# main_board.net
KiCad netlist of a schematic drawn in EAGLE
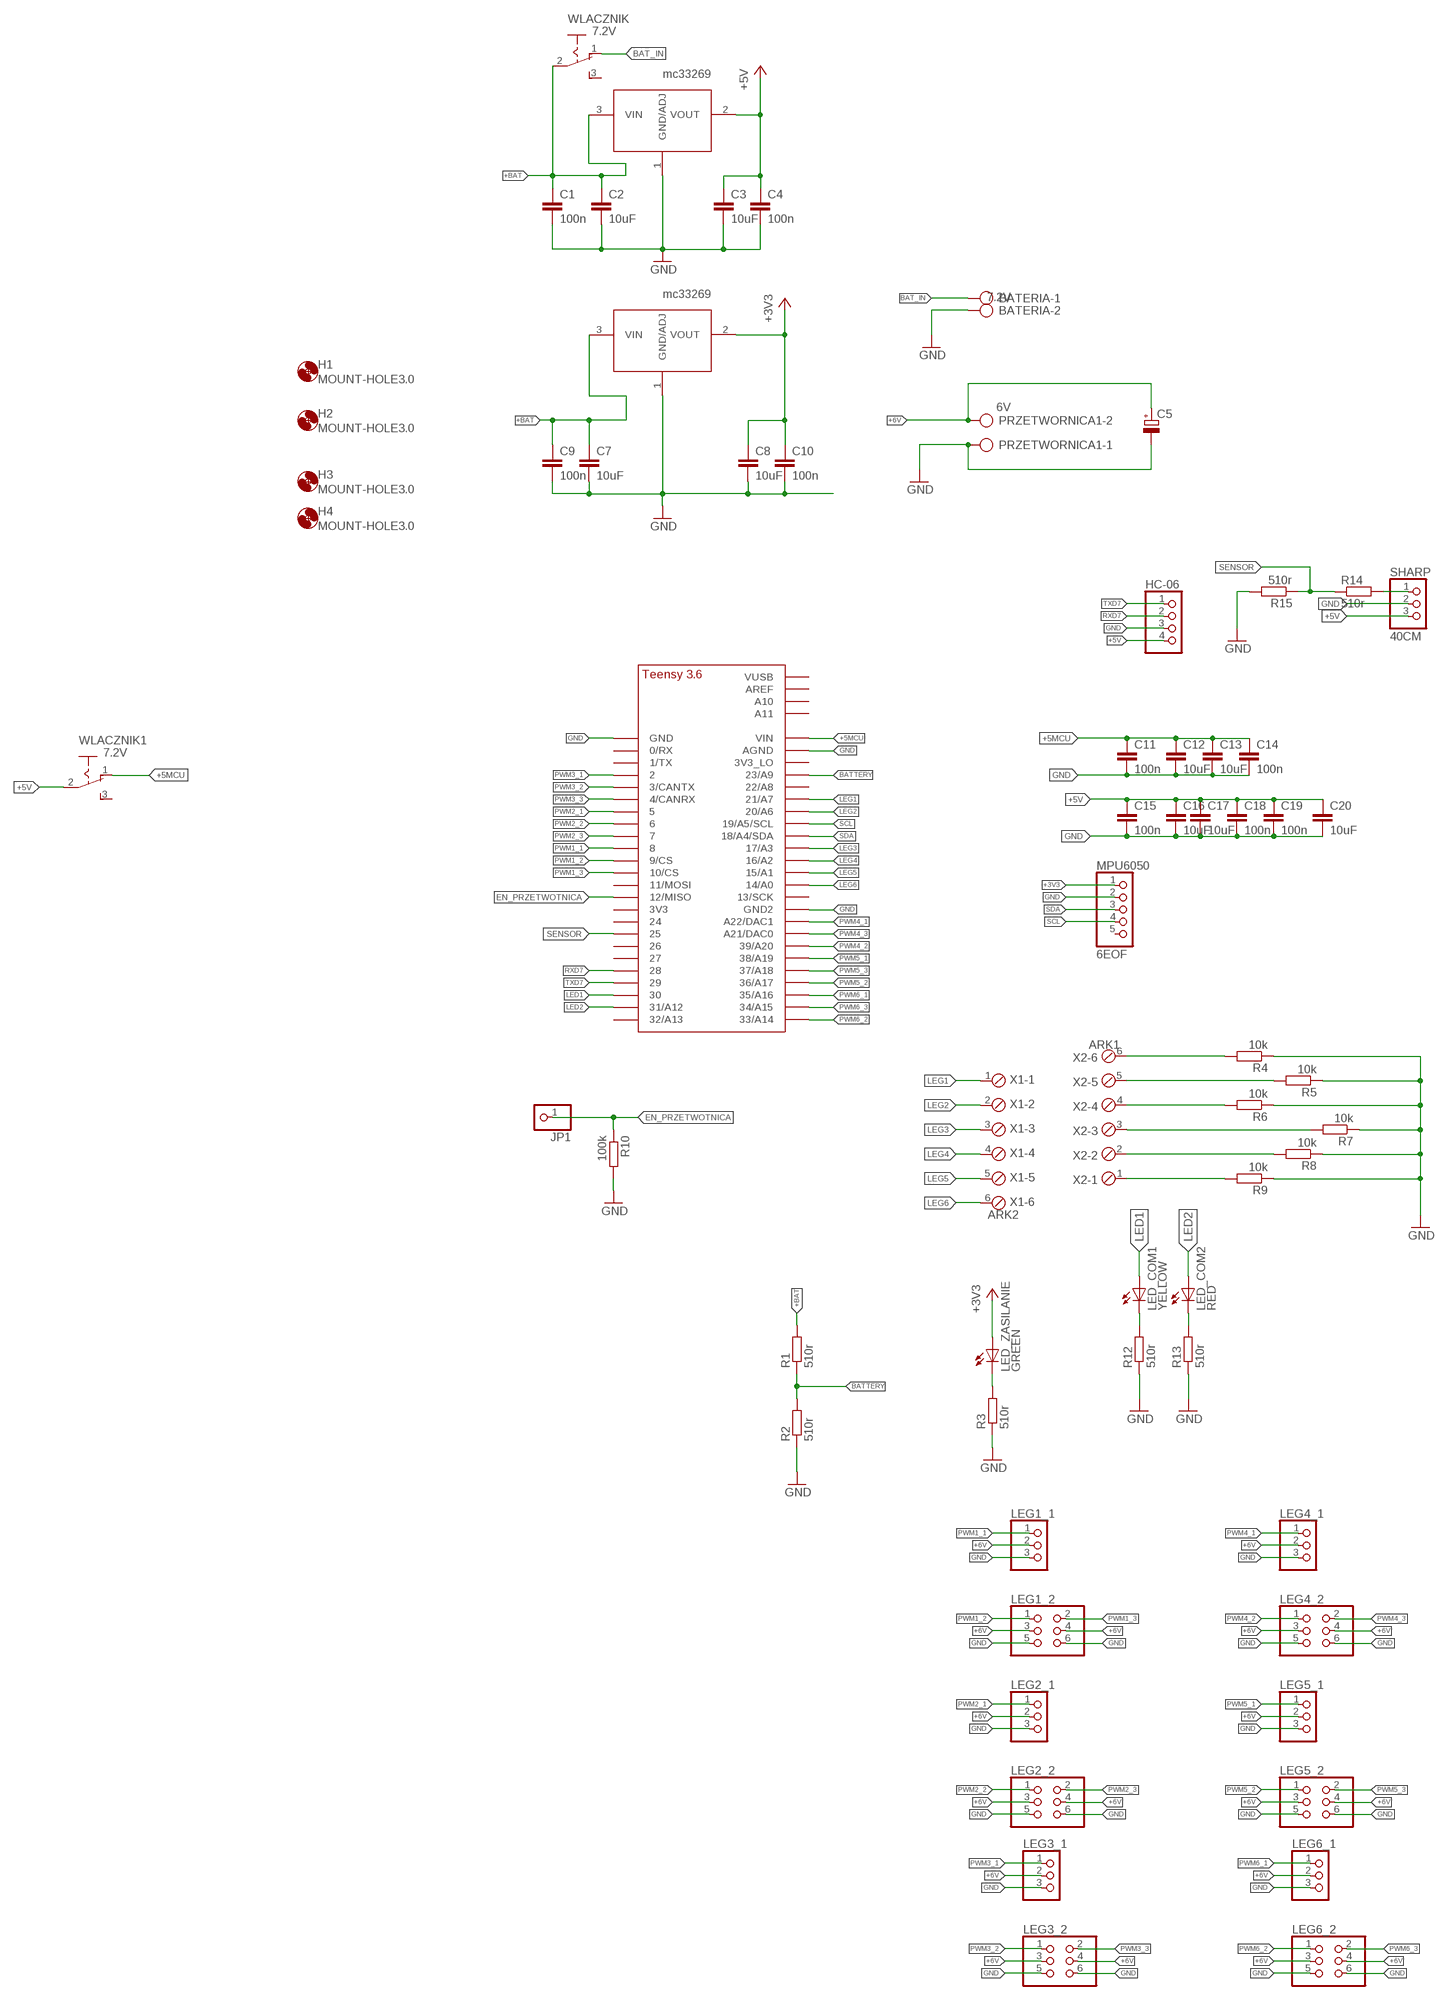
[diagram p0: schematic, sheet 1]

(export (version "E")
  (design (tool "Eeschema 10.0.6"))
  (components
    (comp (ref "3V")
      (value "MC33269")
      (footprint "eagle-import:TO220")
      (libsource (lib "eagle-import") (part "MC33269"))
    )
    (comp (ref "5V")
      (value "MC33269")
      (footprint "eagle-import:TO220")
      (libsource (lib "eagle-import") (part "MC33269"))
    )
    (comp (ref "BATERIA")
      (value "7.2V")
      (footprint "eagle-import:AK300_2")
      (libsource (lib "eagle-import") (part "AK300/2"))
    )
    (comp (ref "C1")
      (value "100n")
      (footprint "eagle-import:C0805")
      (libsource (lib "eagle-import") (part "C-EUC0805"))
    )
    (comp (ref "C2")
      (value "10uF")
      (footprint "eagle-import:C1206")
      (libsource (lib "eagle-import") (part "C-EUC1206"))
    )
    (comp (ref "C3")
      (value "10uF")
      (footprint "eagle-import:C1206")
      (libsource (lib "eagle-import") (part "C-EUC1206"))
    )
    (comp (ref "C4")
      (value "100n")
      (footprint "eagle-import:C0805")
      (libsource (lib "eagle-import") (part "C-EUC0805"))
    )
    (comp (ref "C5")
      (value "CPOL-EU150CLZ-1014")
      (footprint "eagle-import:150CLZ-1014")
      (libsource (lib "eagle-import") (part "CPOL-EU150CLZ-1014"))
    )
    (comp (ref "C7")
      (value "10uF")
      (footprint "eagle-import:C1206")
      (libsource (lib "eagle-import") (part "C-EUC1206"))
    )
    (comp (ref "C8")
      (value "10uF")
      (footprint "eagle-import:C1206")
      (libsource (lib "eagle-import") (part "C-EUC1206"))
    )
    (comp (ref "C9")
      (value "100n")
      (footprint "eagle-import:C0805")
      (libsource (lib "eagle-import") (part "C-EUC0805"))
    )
    (comp (ref "C10")
      (value "100n")
      (footprint "eagle-import:C0805")
      (libsource (lib "eagle-import") (part "C-EUC0805"))
    )
    (comp (ref "C11")
      (value "100n")
      (footprint "eagle-import:C0805")
      (libsource (lib "eagle-import") (part "C-EUC0805"))
    )
    (comp (ref "C12")
      (value "10uF")
      (footprint "eagle-import:C1206")
      (libsource (lib "eagle-import") (part "C-EUC1206"))
    )
    (comp (ref "C13")
      (value "10uF")
      (footprint "eagle-import:C1206")
      (libsource (lib "eagle-import") (part "C-EUC1206"))
    )
    (comp (ref "C14")
      (value "100n")
      (footprint "eagle-import:C0805")
      (libsource (lib "eagle-import") (part "C-EUC0805"))
    )
    (comp (ref "C15")
      (value "100n")
      (footprint "eagle-import:C0805")
      (libsource (lib "eagle-import") (part "C-EUC0805"))
    )
    (comp (ref "C16")
      (value "10uF")
      (footprint "eagle-import:C1206")
      (libsource (lib "eagle-import") (part "C-EUC1206"))
    )
    (comp (ref "C17")
      (value "10uF")
      (footprint "eagle-import:C1206")
      (libsource (lib "eagle-import") (part "C-EUC1206"))
    )
    (comp (ref "C18")
      (value "100n")
      (footprint "eagle-import:C0805")
      (libsource (lib "eagle-import") (part "C-EUC0805"))
    )
    (comp (ref "C19")
      (value "100n")
      (footprint "eagle-import:C0805")
      (libsource (lib "eagle-import") (part "C-EUC0805"))
    )
    (comp (ref "C20")
      (value "10uF")
      (footprint "eagle-import:C1206")
      (libsource (lib "eagle-import") (part "C-EUC1206"))
    )
    (comp (ref "H1")
      (value "MOUNT-HOLE3.0")
      (footprint "eagle-import:3,0")
      (libsource (lib "eagle-import") (part "MOUNT-HOLE3.0"))
    )
    (comp (ref "H2")
      (value "MOUNT-HOLE3.0")
      (footprint "eagle-import:3,0")
      (libsource (lib "eagle-import") (part "MOUNT-HOLE3.0"))
    )
    (comp (ref "H3")
      (value "MOUNT-HOLE3.0")
      (footprint "eagle-import:3,0")
      (libsource (lib "eagle-import") (part "MOUNT-HOLE3.0"))
    )
    (comp (ref "H4")
      (value "MOUNT-HOLE3.0")
      (footprint "eagle-import:3,0")
      (libsource (lib "eagle-import") (part "MOUNT-HOLE3.0"))
    )
    (comp (ref "HC-06")
      (value "PINHD-1X4")
      (footprint "eagle-import:1X04")
      (libsource (lib "eagle-import") (part "PINHD-1X4"))
    )
    (comp (ref "JP1")
      (value "PINHD-1X1")
      (footprint "eagle-import:1X01")
      (libsource (lib "eagle-import") (part "PINHD-1X1"))
    )
    (comp (ref "LED_COM1")
      (value "YELLOW")
      (footprint "eagle-import:SML0805")
      (libsource (lib "eagle-import") (part "LEDSML0805"))
    )
    (comp (ref "LED_COM2")
      (value "RED")
      (footprint "eagle-import:SML0805")
      (libsource (lib "eagle-import") (part "LEDSML0805"))
    )
    (comp (ref "LED_ZASILANIE")
      (value "GREEN")
      (footprint "eagle-import:SML0805")
      (libsource (lib "eagle-import") (part "LEDSML0805"))
    )
    (comp (ref "LEG1_1")
      (value "PINHD-1X3")
      (footprint "eagle-import:1X03")
      (libsource (lib "eagle-import") (part "PINHD-1X3"))
    )
    (comp (ref "LEG1_2")
      (value "PINHD-2X3")
      (footprint "eagle-import:2X03")
      (libsource (lib "eagle-import") (part "PINHD-2X3"))
    )
    (comp (ref "LEG2_1")
      (value "PINHD-1X3")
      (footprint "eagle-import:1X03")
      (libsource (lib "eagle-import") (part "PINHD-1X3"))
    )
    (comp (ref "LEG2_2")
      (value "PINHD-2X3")
      (footprint "eagle-import:2X03")
      (libsource (lib "eagle-import") (part "PINHD-2X3"))
    )
    (comp (ref "LEG3_1")
      (value "PINHD-1X3")
      (footprint "eagle-import:1X03")
      (libsource (lib "eagle-import") (part "PINHD-1X3"))
    )
    (comp (ref "LEG3_2")
      (value "PINHD-2X3")
      (footprint "eagle-import:2X03")
      (libsource (lib "eagle-import") (part "PINHD-2X3"))
    )
    (comp (ref "LEG4_1")
      (value "PINHD-1X3")
      (footprint "eagle-import:1X03")
      (libsource (lib "eagle-import") (part "PINHD-1X3"))
    )
    (comp (ref "LEG4_2")
      (value "PINHD-2X3")
      (footprint "eagle-import:2X03")
      (libsource (lib "eagle-import") (part "PINHD-2X3"))
    )
    (comp (ref "LEG5_1")
      (value "PINHD-1X3")
      (footprint "eagle-import:1X03")
      (libsource (lib "eagle-import") (part "PINHD-1X3"))
    )
    (comp (ref "LEG5_2")
      (value "PINHD-2X3")
      (footprint "eagle-import:2X03")
      (libsource (lib "eagle-import") (part "PINHD-2X3"))
    )
    (comp (ref "LEG6_1")
      (value "PINHD-1X3")
      (footprint "eagle-import:1X03")
      (libsource (lib "eagle-import") (part "PINHD-1X3"))
    )
    (comp (ref "LEG6_2")
      (value "PINHD-2X3")
      (footprint "eagle-import:2X03")
      (libsource (lib "eagle-import") (part "PINHD-2X3"))
    )
    (comp (ref "MPU6050")
      (value "6EOF")
      (footprint "eagle-import:1X05")
      (libsource (lib "eagle-import") (part "PINHD-1X5"))
    )
    (comp (ref "PRZETWORNICA1")
      (value "6V")
      (footprint "eagle-import:AK300_2")
      (libsource (lib "eagle-import") (part "AK300/2"))
    )
    (comp (ref "R1")
      (value "510r")
      (footprint "eagle-import:R0805")
      (libsource (lib "eagle-import") (part "R-EU_R0805"))
    )
    (comp (ref "R2")
      (value "510r")
      (footprint "eagle-import:R0805")
      (libsource (lib "eagle-import") (part "R-EU_R0805"))
    )
    (comp (ref "R3")
      (value "510r")
      (footprint "eagle-import:R0805")
      (libsource (lib "eagle-import") (part "R-EU_R0805"))
    )
    (comp (ref "R4")
      (value "10k")
      (footprint "eagle-import:R0805")
      (libsource (lib "eagle-import") (part "R-EU_R0805"))
    )
    (comp (ref "R5")
      (value "10k")
      (footprint "eagle-import:R0805")
      (libsource (lib "eagle-import") (part "R-EU_R0805"))
    )
    (comp (ref "R6")
      (value "10k")
      (footprint "eagle-import:R0805")
      (libsource (lib "eagle-import") (part "R-EU_R0805"))
    )
    (comp (ref "R7")
      (value "10k")
      (footprint "eagle-import:R0805")
      (libsource (lib "eagle-import") (part "R-EU_R0805"))
    )
    (comp (ref "R8")
      (value "10k")
      (footprint "eagle-import:R0805")
      (libsource (lib "eagle-import") (part "R-EU_R0805"))
    )
    (comp (ref "R9")
      (value "10k")
      (footprint "eagle-import:R0805")
      (libsource (lib "eagle-import") (part "R-EU_R0805"))
    )
    (comp (ref "R10")
      (value "100k")
      (footprint "eagle-import:R0805")
      (libsource (lib "eagle-import") (part "R-EU_R0805"))
    )
    (comp (ref "R12")
      (value "510r")
      (footprint "eagle-import:R0805")
      (libsource (lib "eagle-import") (part "R-EU_R0805"))
    )
    (comp (ref "R13")
      (value "510r")
      (footprint "eagle-import:R0805")
      (libsource (lib "eagle-import") (part "R-EU_R0805"))
    )
    (comp (ref "R14")
      (value "510r")
      (footprint "eagle-import:R0805")
      (libsource (lib "eagle-import") (part "R-EU_R0805"))
    )
    (comp (ref "R15")
      (value "510r")
      (footprint "eagle-import:R0805")
      (libsource (lib "eagle-import") (part "R-EU_R0805"))
    )
    (comp (ref "SHARP")
      (value "40CM")
      (footprint "eagle-import:1X03")
      (libsource (lib "eagle-import") (part "PINHD-1X3"))
    )
    (comp (ref "TEENSY41")
      (value "TEENSY_3.5/3.6_BASIC")
      (footprint "eagle-import:TEENSY_3.5_3.6_BASIC")
      (libsource (lib "eagle-import") (part "TEENSY_3.5/3.6_BASIC"))
    )
    (comp (ref "WLACZNIK")
      (value "7.2V")
      (footprint "eagle-import:255SB")
      (libsource (lib "eagle-import") (part "255SB"))
    )
    (comp (ref "WLACZNIK1")
      (value "7.2V")
      (footprint "eagle-import:255SB")
      (libsource (lib "eagle-import") (part "255SB"))
    )
    (comp (ref "X1")
      (value "ARK2")
      (footprint "eagle-import:6POL254")
      (libsource (lib "eagle-import") (part "MPT6"))
    )
    (comp (ref "X2")
      (value "ARK1")
      (footprint "eagle-import:6POL254")
      (libsource (lib "eagle-import") (part "MPT6"))
    )
  )
  (nets
    (net (code "1") (name "+3V3") (class "Default")
      (node (ref "3V") (pin "2") (pinfunction "VOUT_2") (pintype "bidirectional"))
      (node (ref "C10") (pin "1") (pinfunction "1_1") (pintype "passive"))
      (node (ref "C8") (pin "1") (pinfunction "1_1") (pintype "passive"))
      (node (ref "LED_ZASILANIE") (pin "A") (pinfunction "A_A") (pintype "passive"))
      (node (ref "MPU6050") (pin "1") (pinfunction "1_1") (pintype "passive"))
    )
    (net (code "2") (name "+5MCU") (class "Default")
      (node (ref "C11") (pin "1") (pinfunction "1_1") (pintype "passive"))
      (node (ref "C12") (pin "1") (pinfunction "1_1") (pintype "passive"))
      (node (ref "C13") (pin "1") (pinfunction "1_1") (pintype "passive"))
      (node (ref "C14") (pin "1") (pinfunction "1_1") (pintype "passive"))
      (node (ref "TEENSY41") (pin "VIN") (pinfunction "VIN_VIN") (pintype "bidirectional"))
      (node (ref "WLACZNIK1") (pin "1") (pinfunction "O_1") (pintype "passive"))
    )
    (net (code "3") (name "+5V") (class "Default")
      (node (ref "5V") (pin "2") (pinfunction "VOUT_2") (pintype "bidirectional"))
      (node (ref "C15") (pin "1") (pinfunction "1_1") (pintype "passive"))
      (node (ref "C16") (pin "1") (pinfunction "1_1") (pintype "passive"))
      (node (ref "C17") (pin "1") (pinfunction "1_1") (pintype "passive"))
      (node (ref "C18") (pin "1") (pinfunction "1_1") (pintype "passive"))
      (node (ref "C19") (pin "1") (pinfunction "1_1") (pintype "passive"))
      (node (ref "C20") (pin "1") (pinfunction "1_1") (pintype "passive"))
      (node (ref "C3") (pin "1") (pinfunction "1_1") (pintype "passive"))
      (node (ref "C4") (pin "1") (pinfunction "1_1") (pintype "passive"))
      (node (ref "HC-06") (pin "4") (pinfunction "4_4") (pintype "passive"))
      (node (ref "SHARP") (pin "3") (pinfunction "3_3") (pintype "passive"))
      (node (ref "WLACZNIK1") (pin "2") (pinfunction "P_2") (pintype "passive"))
    )
    (net (code "4") (name "+6V") (class "Default")
      (node (ref "C5") (pin "+") (pinfunction "+_+") (pintype "passive"))
      (node (ref "LEG1_1") (pin "2") (pinfunction "2_2") (pintype "passive"))
      (node (ref "LEG1_2") (pin "3") (pinfunction "3_3") (pintype "passive"))
      (node (ref "LEG1_2") (pin "4") (pinfunction "4_4") (pintype "passive"))
      (node (ref "LEG2_1") (pin "2") (pinfunction "2_2") (pintype "passive"))
      (node (ref "LEG2_2") (pin "3") (pinfunction "3_3") (pintype "passive"))
      (node (ref "LEG2_2") (pin "4") (pinfunction "4_4") (pintype "passive"))
      (node (ref "LEG3_1") (pin "2") (pinfunction "2_2") (pintype "passive"))
      (node (ref "LEG3_2") (pin "3") (pinfunction "3_3") (pintype "passive"))
      (node (ref "LEG3_2") (pin "4") (pinfunction "4_4") (pintype "passive"))
      (node (ref "LEG4_1") (pin "2") (pinfunction "2_2") (pintype "passive"))
      (node (ref "LEG4_2") (pin "3") (pinfunction "3_3") (pintype "passive"))
      (node (ref "LEG4_2") (pin "4") (pinfunction "4_4") (pintype "passive"))
      (node (ref "LEG5_1") (pin "2") (pinfunction "2_2") (pintype "passive"))
      (node (ref "LEG5_2") (pin "3") (pinfunction "3_3") (pintype "passive"))
      (node (ref "LEG5_2") (pin "4") (pinfunction "4_4") (pintype "passive"))
      (node (ref "LEG6_1") (pin "2") (pinfunction "2_2") (pintype "passive"))
      (node (ref "LEG6_2") (pin "3") (pinfunction "3_3") (pintype "passive"))
      (node (ref "LEG6_2") (pin "4") (pinfunction "4_4") (pintype "passive"))
      (node (ref "PRZETWORNICA1") (pin "2") (pinfunction "KL_2") (pintype "passive"))
    )
    (net (code "5") (name "+BAT") (class "Default")
      (node (ref "3V") (pin "3") (pinfunction "VIN_3") (pintype "bidirectional"))
      (node (ref "5V") (pin "3") (pinfunction "VIN_3") (pintype "bidirectional"))
      (node (ref "C1") (pin "1") (pinfunction "1_1") (pintype "passive"))
      (node (ref "C2") (pin "1") (pinfunction "1_1") (pintype "passive"))
      (node (ref "C7") (pin "1") (pinfunction "1_1") (pintype "passive"))
      (node (ref "C9") (pin "1") (pinfunction "1_1") (pintype "passive"))
      (node (ref "R1") (pin "2") (pinfunction "2_2") (pintype "passive"))
      (node (ref "WLACZNIK") (pin "2") (pinfunction "P_2") (pintype "passive"))
    )
    (net (code "6") (name "BATTERY") (class "Default")
      (node (ref "R1") (pin "1") (pinfunction "1_1") (pintype "passive"))
      (node (ref "R2") (pin "2") (pinfunction "2_2") (pintype "passive"))
      (node (ref "TEENSY41") (pin "23/A9") (pinfunction "23/A9_23/A9") (pintype "bidirectional"))
    )
    (net (code "7") (name "BAT_IN") (class "Default")
      (node (ref "BATERIA") (pin "1") (pinfunction "KL_1") (pintype "passive"))
      (node (ref "WLACZNIK") (pin "1") (pinfunction "O_1") (pintype "passive"))
    )
    (net (code "8") (name "EN_PRZETWOTNICA") (class "Default")
      (node (ref "JP1") (pin "1") (pinfunction "1_1") (pintype "passive"))
      (node (ref "R10") (pin "1") (pinfunction "1_1") (pintype "passive"))
      (node (ref "TEENSY41") (pin "12/MISO") (pinfunction "12/MISO_12/MISO") (pintype "bidirectional"))
    )
    (net (code "9") (name "GND") (class "Default")
      (node (ref "3V") (pin "1") (pinfunction "GND/ADJ_1") (pintype "bidirectional"))
      (node (ref "5V") (pin "1") (pinfunction "GND/ADJ_1") (pintype "bidirectional"))
      (node (ref "BATERIA") (pin "2") (pinfunction "KL_2") (pintype "passive"))
      (node (ref "C1") (pin "2") (pinfunction "2_2") (pintype "passive"))
      (node (ref "C10") (pin "2") (pinfunction "2_2") (pintype "passive"))
      (node (ref "C11") (pin "2") (pinfunction "2_2") (pintype "passive"))
      (node (ref "C12") (pin "2") (pinfunction "2_2") (pintype "passive"))
      (node (ref "C13") (pin "2") (pinfunction "2_2") (pintype "passive"))
      (node (ref "C14") (pin "2") (pinfunction "2_2") (pintype "passive"))
      (node (ref "C15") (pin "2") (pinfunction "2_2") (pintype "passive"))
      (node (ref "C16") (pin "2") (pinfunction "2_2") (pintype "passive"))
      (node (ref "C17") (pin "2") (pinfunction "2_2") (pintype "passive"))
      (node (ref "C18") (pin "2") (pinfunction "2_2") (pintype "passive"))
      (node (ref "C19") (pin "2") (pinfunction "2_2") (pintype "passive"))
      (node (ref "C2") (pin "2") (pinfunction "2_2") (pintype "passive"))
      (node (ref "C20") (pin "2") (pinfunction "2_2") (pintype "passive"))
      (node (ref "C3") (pin "2") (pinfunction "2_2") (pintype "passive"))
      (node (ref "C4") (pin "2") (pinfunction "2_2") (pintype "passive"))
      (node (ref "C5") (pin "-") (pinfunction "-_-") (pintype "passive"))
      (node (ref "C7") (pin "2") (pinfunction "2_2") (pintype "passive"))
      (node (ref "C8") (pin "2") (pinfunction "2_2") (pintype "passive"))
      (node (ref "C9") (pin "2") (pinfunction "2_2") (pintype "passive"))
      (node (ref "HC-06") (pin "3") (pinfunction "3_3") (pintype "passive"))
      (node (ref "LEG1_1") (pin "3") (pinfunction "3_3") (pintype "passive"))
      (node (ref "LEG1_2") (pin "5") (pinfunction "5_5") (pintype "passive"))
      (node (ref "LEG1_2") (pin "6") (pinfunction "6_6") (pintype "passive"))
      (node (ref "LEG2_1") (pin "3") (pinfunction "3_3") (pintype "passive"))
      (node (ref "LEG2_2") (pin "5") (pinfunction "5_5") (pintype "passive"))
      (node (ref "LEG2_2") (pin "6") (pinfunction "6_6") (pintype "passive"))
      (node (ref "LEG3_1") (pin "3") (pinfunction "3_3") (pintype "passive"))
      (node (ref "LEG3_2") (pin "5") (pinfunction "5_5") (pintype "passive"))
      (node (ref "LEG3_2") (pin "6") (pinfunction "6_6") (pintype "passive"))
      (node (ref "LEG4_1") (pin "3") (pinfunction "3_3") (pintype "passive"))
      (node (ref "LEG4_2") (pin "5") (pinfunction "5_5") (pintype "passive"))
      (node (ref "LEG4_2") (pin "6") (pinfunction "6_6") (pintype "passive"))
      (node (ref "LEG5_1") (pin "3") (pinfunction "3_3") (pintype "passive"))
      (node (ref "LEG5_2") (pin "5") (pinfunction "5_5") (pintype "passive"))
      (node (ref "LEG5_2") (pin "6") (pinfunction "6_6") (pintype "passive"))
      (node (ref "LEG6_1") (pin "3") (pinfunction "3_3") (pintype "passive"))
      (node (ref "LEG6_2") (pin "5") (pinfunction "5_5") (pintype "passive"))
      (node (ref "LEG6_2") (pin "6") (pinfunction "6_6") (pintype "passive"))
      (node (ref "MPU6050") (pin "2") (pinfunction "2_2") (pintype "passive"))
      (node (ref "PRZETWORNICA1") (pin "1") (pinfunction "KL_1") (pintype "passive"))
      (node (ref "R10") (pin "2") (pinfunction "2_2") (pintype "passive"))
      (node (ref "R12") (pin "1") (pinfunction "1_1") (pintype "passive"))
      (node (ref "R13") (pin "1") (pinfunction "1_1") (pintype "passive"))
      (node (ref "R15") (pin "2") (pinfunction "2_2") (pintype "passive"))
      (node (ref "R2") (pin "1") (pinfunction "1_1") (pintype "passive"))
      (node (ref "R3") (pin "1") (pinfunction "1_1") (pintype "passive"))
      (node (ref "R4") (pin "1") (pinfunction "1_1") (pintype "passive"))
      (node (ref "R5") (pin "1") (pinfunction "1_1") (pintype "passive"))
      (node (ref "R6") (pin "1") (pinfunction "1_1") (pintype "passive"))
      (node (ref "R7") (pin "1") (pinfunction "1_1") (pintype "passive"))
      (node (ref "R8") (pin "1") (pinfunction "1_1") (pintype "passive"))
      (node (ref "R9") (pin "1") (pinfunction "1_1") (pintype "passive"))
      (node (ref "SHARP") (pin "2") (pinfunction "2_2") (pintype "passive"))
      (node (ref "TEENSY41") (pin "AGND") (pinfunction "AGND_AGND") (pintype "bidirectional"))
      (node (ref "TEENSY41") (pin "GND") (pinfunction "GND_GND") (pintype "bidirectional"))
      (node (ref "TEENSY41") (pin "GND2") (pinfunction "GND2_GND2") (pintype "bidirectional"))
    )
    (net (code "10") (name "LED1") (class "Default")
      (node (ref "LED_COM1") (pin "A") (pinfunction "A_A") (pintype "passive"))
      (node (ref "TEENSY41") (pin "30") (pinfunction "30_30") (pintype "bidirectional"))
    )
    (net (code "11") (name "LED2") (class "Default")
      (node (ref "LED_COM2") (pin "A") (pinfunction "A_A") (pintype "passive"))
      (node (ref "TEENSY41") (pin "31/A12") (pinfunction "31/A12_31/A12") (pintype "bidirectional"))
    )
    (net (code "12") (name "LEG1") (class "Default")
      (node (ref "TEENSY41") (pin "21/A7") (pinfunction "21/A7_21/A7") (pintype "bidirectional"))
      (node (ref "X1") (pin "1") (pinfunction "1_1") (pintype "passive"))
    )
    (net (code "13") (name "LEG2") (class "Default")
      (node (ref "TEENSY41") (pin "20/A6") (pinfunction "20/A6_20/A6") (pintype "bidirectional"))
      (node (ref "X1") (pin "2") (pinfunction "1_2") (pintype "passive"))
    )
    (net (code "14") (name "LEG3") (class "Default")
      (node (ref "TEENSY41") (pin "17/A3") (pinfunction "17/A3_17/A3") (pintype "bidirectional"))
      (node (ref "X1") (pin "3") (pinfunction "1_3") (pintype "passive"))
    )
    (net (code "15") (name "LEG4") (class "Default")
      (node (ref "TEENSY41") (pin "16/A2") (pinfunction "16/A2_16/A2") (pintype "bidirectional"))
      (node (ref "X1") (pin "4") (pinfunction "1_4") (pintype "passive"))
    )
    (net (code "16") (name "LEG5") (class "Default")
      (node (ref "TEENSY41") (pin "15/A1") (pinfunction "15/A1_15/A1") (pintype "bidirectional"))
      (node (ref "X1") (pin "5") (pinfunction "1_5") (pintype "passive"))
    )
    (net (code "17") (name "LEG6") (class "Default")
      (node (ref "TEENSY41") (pin "14/A0") (pinfunction "14/A0_14/A0") (pintype "bidirectional"))
      (node (ref "X1") (pin "6") (pinfunction "1_6") (pintype "passive"))
    )
    (net (code "18") (name "Net-(LED_COM1-PadC)") (class "Default")
      (node (ref "LED_COM1") (pin "C") (pinfunction "C_C") (pintype "passive"))
      (node (ref "R12") (pin "2") (pinfunction "2_2") (pintype "passive"))
    )
    (net (code "19") (name "Net-(LED_COM2-PadC)") (class "Default")
      (node (ref "LED_COM2") (pin "C") (pinfunction "C_C") (pintype "passive"))
      (node (ref "R13") (pin "2") (pinfunction "2_2") (pintype "passive"))
    )
    (net (code "20") (name "Net-(LED_ZASILANIE-PadC)") (class "Default")
      (node (ref "LED_ZASILANIE") (pin "C") (pinfunction "C_C") (pintype "passive"))
      (node (ref "R3") (pin "2") (pinfunction "2_2") (pintype "passive"))
    )
    (net (code "21") (name "Net-(R9-Pad2)") (class "Default")
      (node (ref "R9") (pin "2") (pinfunction "2_2") (pintype "passive"))
      (node (ref "X2") (pin "1") (pinfunction "1_1") (pintype "passive"))
    )
    (net (code "22") (name "Net-(R14-Pad2)") (class "Default")
      (node (ref "R14") (pin "2") (pinfunction "2_2") (pintype "passive"))
      (node (ref "SHARP") (pin "1") (pinfunction "1_1") (pintype "passive"))
    )
    (net (code "23") (name "Net-(X2B-1)") (class "Default")
      (node (ref "R8") (pin "2") (pinfunction "2_2") (pintype "passive"))
      (node (ref "X2") (pin "2") (pinfunction "1_2") (pintype "passive"))
    )
    (net (code "24") (name "Net-(X2C-1)") (class "Default")
      (node (ref "R7") (pin "2") (pinfunction "2_2") (pintype "passive"))
      (node (ref "X2") (pin "3") (pinfunction "1_3") (pintype "passive"))
    )
    (net (code "25") (name "Net-(X2D-1)") (class "Default")
      (node (ref "R6") (pin "2") (pinfunction "2_2") (pintype "passive"))
      (node (ref "X2") (pin "4") (pinfunction "1_4") (pintype "passive"))
    )
    (net (code "26") (name "Net-(X2E-1)") (class "Default")
      (node (ref "R5") (pin "2") (pinfunction "2_2") (pintype "passive"))
      (node (ref "X2") (pin "5") (pinfunction "1_5") (pintype "passive"))
    )
    (net (code "27") (name "Net-(X2F-1)") (class "Default")
      (node (ref "R4") (pin "2") (pinfunction "2_2") (pintype "passive"))
      (node (ref "X2") (pin "6") (pinfunction "1_6") (pintype "passive"))
    )
    (net (code "28") (name "PWM1_1") (class "Default")
      (node (ref "LEG1_1") (pin "1") (pinfunction "1_1") (pintype "passive"))
      (node (ref "TEENSY41") (pin "8") (pinfunction "8_8") (pintype "bidirectional"))
    )
    (net (code "29") (name "PWM1_2") (class "Default")
      (node (ref "LEG1_2") (pin "1") (pinfunction "1_1") (pintype "passive"))
      (node (ref "TEENSY41") (pin "9/CS") (pinfunction "9/CS_9/CS") (pintype "bidirectional"))
    )
    (net (code "30") (name "PWM1_3") (class "Default")
      (node (ref "LEG1_2") (pin "2") (pinfunction "2_2") (pintype "passive"))
      (node (ref "TEENSY41") (pin "10/CS") (pinfunction "10/CS_10/CS") (pintype "bidirectional"))
    )
    (net (code "31") (name "PWM2_1") (class "Default")
      (node (ref "LEG2_1") (pin "1") (pinfunction "1_1") (pintype "passive"))
      (node (ref "TEENSY41") (pin "5") (pinfunction "5_5") (pintype "bidirectional"))
    )
    (net (code "32") (name "PWM2_2") (class "Default")
      (node (ref "LEG2_2") (pin "1") (pinfunction "1_1") (pintype "passive"))
      (node (ref "TEENSY41") (pin "6") (pinfunction "6_6") (pintype "bidirectional"))
    )
    (net (code "33") (name "PWM2_3") (class "Default")
      (node (ref "LEG2_2") (pin "2") (pinfunction "2_2") (pintype "passive"))
      (node (ref "TEENSY41") (pin "7") (pinfunction "7_7") (pintype "bidirectional"))
    )
    (net (code "34") (name "PWM3_1") (class "Default")
      (node (ref "LEG3_1") (pin "1") (pinfunction "1_1") (pintype "passive"))
      (node (ref "TEENSY41") (pin "2") (pinfunction "2_2") (pintype "bidirectional"))
    )
    (net (code "35") (name "PWM3_2") (class "Default")
      (node (ref "LEG3_2") (pin "1") (pinfunction "1_1") (pintype "passive"))
      (node (ref "TEENSY41") (pin "3/CANTX") (pinfunction "3/CANTX_3/CANTX") (pintype "bidirectional"))
    )
    (net (code "36") (name "PWM3_3") (class "Default")
      (node (ref "LEG3_2") (pin "2") (pinfunction "2_2") (pintype "passive"))
      (node (ref "TEENSY41") (pin "4/CANRX") (pinfunction "4/CANRX_4/CANRX") (pintype "bidirectional"))
    )
    (net (code "37") (name "PWM4_1") (class "Default")
      (node (ref "LEG4_1") (pin "1") (pinfunction "1_1") (pintype "passive"))
      (node (ref "TEENSY41") (pin "A22/DAC1") (pinfunction "A22/DAC1_A22/DAC1") (pintype "bidirectional"))
    )
    (net (code "38") (name "PWM4_2") (class "Default")
      (node (ref "LEG4_2") (pin "1") (pinfunction "1_1") (pintype "passive"))
      (node (ref "TEENSY41") (pin "39/A20") (pinfunction "39/A20_39/A20") (pintype "bidirectional"))
    )
    (net (code "39") (name "PWM4_3") (class "Default")
      (node (ref "LEG4_2") (pin "2") (pinfunction "2_2") (pintype "passive"))
      (node (ref "TEENSY41") (pin "21/DAC0") (pinfunction "A21/DAC0_21/DAC0") (pintype "bidirectional"))
    )
    (net (code "40") (name "PWM5_1") (class "Default")
      (node (ref "LEG5_1") (pin "1") (pinfunction "1_1") (pintype "passive"))
      (node (ref "TEENSY41") (pin "38/A19") (pinfunction "38/A19_38/A19") (pintype "bidirectional"))
    )
    (net (code "41") (name "PWM5_2") (class "Default")
      (node (ref "LEG5_2") (pin "1") (pinfunction "1_1") (pintype "passive"))
      (node (ref "TEENSY41") (pin "36/A17") (pinfunction "36/A17_36/A17") (pintype "bidirectional"))
    )
    (net (code "42") (name "PWM5_3") (class "Default")
      (node (ref "LEG5_2") (pin "2") (pinfunction "2_2") (pintype "passive"))
      (node (ref "TEENSY41") (pin "37/A18") (pinfunction "37/A18_37/A18") (pintype "bidirectional"))
    )
    (net (code "43") (name "PWM6_1") (class "Default")
      (node (ref "LEG6_1") (pin "1") (pinfunction "1_1") (pintype "passive"))
      (node (ref "TEENSY41") (pin "35/A16") (pinfunction "35/A16_35/A16") (pintype "bidirectional"))
    )
    (net (code "44") (name "PWM6_2") (class "Default")
      (node (ref "LEG6_2") (pin "1") (pinfunction "1_1") (pintype "passive"))
      (node (ref "TEENSY41") (pin "33/A14") (pinfunction "33/A14_33/A14") (pintype "bidirectional"))
    )
    (net (code "45") (name "PWM6_3") (class "Default")
      (node (ref "LEG6_2") (pin "2") (pinfunction "2_2") (pintype "passive"))
      (node (ref "TEENSY41") (pin "34/A15") (pinfunction "34/A15_34/A15") (pintype "bidirectional"))
    )
    (net (code "46") (name "RXD7") (class "Default")
      (node (ref "HC-06") (pin "2") (pinfunction "2_2") (pintype "passive"))
      (node (ref "TEENSY41") (pin "28") (pinfunction "28_28") (pintype "bidirectional"))
    )
    (net (code "47") (name "SCL") (class "Default")
      (node (ref "MPU6050") (pin "4") (pinfunction "4_4") (pintype "passive"))
      (node (ref "TEENSY41") (pin "19/A5/SCL") (pinfunction "19/A5/SCL_19/A5/SCL") (pintype "bidirectional"))
    )
    (net (code "48") (name "SDA") (class "Default")
      (node (ref "MPU6050") (pin "3") (pinfunction "3_3") (pintype "passive"))
      (node (ref "TEENSY41") (pin "18/A4/SDA") (pinfunction "18/A4/SDA_18/A4/SDA") (pintype "bidirectional"))
    )
    (net (code "49") (name "SENSOR") (class "Default")
      (node (ref "R14") (pin "1") (pinfunction "1_1") (pintype "passive"))
      (node (ref "R15") (pin "1") (pinfunction "1_1") (pintype "passive"))
      (node (ref "TEENSY41") (pin "25") (pinfunction "25_25") (pintype "bidirectional"))
    )
    (net (code "50") (name "TXD7") (class "Default")
      (node (ref "HC-06") (pin "1") (pinfunction "1_1") (pintype "passive"))
      (node (ref "TEENSY41") (pin "29") (pinfunction "29_29") (pintype "bidirectional"))
    )
    (net (code "51") (name "unconnected-(MPU6050-Pad5)") (class "Default")
      (node (ref "MPU6050") (pin "5") (pinfunction "5_5") (pintype "passive"))
    )
    (net (code "52") (name "unconnected-(TEENSY41-Pad0{slash}RX)") (class "Default")
      (node (ref "TEENSY41") (pin "0/RX") (pinfunction "0/RX_0/RX") (pintype "bidirectional"))
    )
    (net (code "53") (name "unconnected-(TEENSY41-Pad1{slash}TX)") (class "Default")
      (node (ref "TEENSY41") (pin "1/TX") (pinfunction "1/TX_1/TX") (pintype "bidirectional"))
    )
    (net (code "54") (name "unconnected-(TEENSY41-Pad3V3)") (class "Default")
      (node (ref "TEENSY41") (pin "3V3") (pinfunction "3V3_3V3") (pintype "bidirectional"))
    )
    (net (code "55") (name "unconnected-(TEENSY41-Pad3V3_LO)") (class "Default")
      (node (ref "TEENSY41") (pin "3V3_LO") (pinfunction "3V3_LO_3V3_LO") (pintype "bidirectional"))
    )
    (net (code "56") (name "unconnected-(TEENSY41-Pad11{slash}MOSI)") (class "Default")
      (node (ref "TEENSY41") (pin "11/MOSI") (pinfunction "11/MOSI_11/MOSI") (pintype "bidirectional"))
    )
    (net (code "57") (name "unconnected-(TEENSY41-Pad13{slash}SCK)") (class "Default")
      (node (ref "TEENSY41") (pin "13/SCK") (pinfunction "13/SCK_13/SCK") (pintype "bidirectional"))
    )
    (net (code "58") (name "unconnected-(TEENSY41-Pad22{slash}A8)") (class "Default")
      (node (ref "TEENSY41") (pin "22/A8") (pinfunction "22/A8_22/A8") (pintype "bidirectional"))
    )
    (net (code "59") (name "unconnected-(TEENSY41-Pad24)") (class "Default")
      (node (ref "TEENSY41") (pin "24") (pinfunction "24_24") (pintype "bidirectional"))
    )
    (net (code "60") (name "unconnected-(TEENSY41-Pad26)") (class "Default")
      (node (ref "TEENSY41") (pin "26") (pinfunction "26_26") (pintype "bidirectional"))
    )
    (net (code "61") (name "unconnected-(TEENSY41-Pad27)") (class "Default")
      (node (ref "TEENSY41") (pin "27") (pinfunction "27_27") (pintype "bidirectional"))
    )
    (net (code "62") (name "unconnected-(TEENSY41-Pad32{slash}A13)") (class "Default")
      (node (ref "TEENSY41") (pin "32/A13") (pinfunction "32/A13_32/A13") (pintype "bidirectional"))
    )
    (net (code "63") (name "unconnected-(TEENSY41-PadA10)") (class "Default")
      (node (ref "TEENSY41") (pin "A10") (pinfunction "A10_A10") (pintype "bidirectional"))
    )
    (net (code "64") (name "unconnected-(TEENSY41-PadA11)") (class "Default")
      (node (ref "TEENSY41") (pin "A11") (pinfunction "A11_A11") (pintype "bidirectional"))
    )
    (net (code "65") (name "unconnected-(TEENSY41-PadAREF)") (class "Default")
      (node (ref "TEENSY41") (pin "AREF") (pinfunction "AREF_AREF") (pintype "bidirectional"))
    )
    (net (code "66") (name "unconnected-(TEENSY41-PadVUSB)") (class "Default")
      (node (ref "TEENSY41") (pin "VUSB") (pinfunction "VUSB_VUSB") (pintype "bidirectional"))
    )
    (net (code "67") (name "unconnected-(WLACZNIK-S-Pad3)") (class "Default")
      (node (ref "WLACZNIK") (pin "3") (pinfunction "S_3") (pintype "passive"))
    )
    (net (code "68") (name "unconnected-(WLACZNIK1-S-Pad3)") (class "Default")
      (node (ref "WLACZNIK1") (pin "3") (pinfunction "S_3") (pintype "passive"))
    )
  )
)
